# SH1_-_POWER.net
KiCad netlist of a schematic drawn in Altium Designer
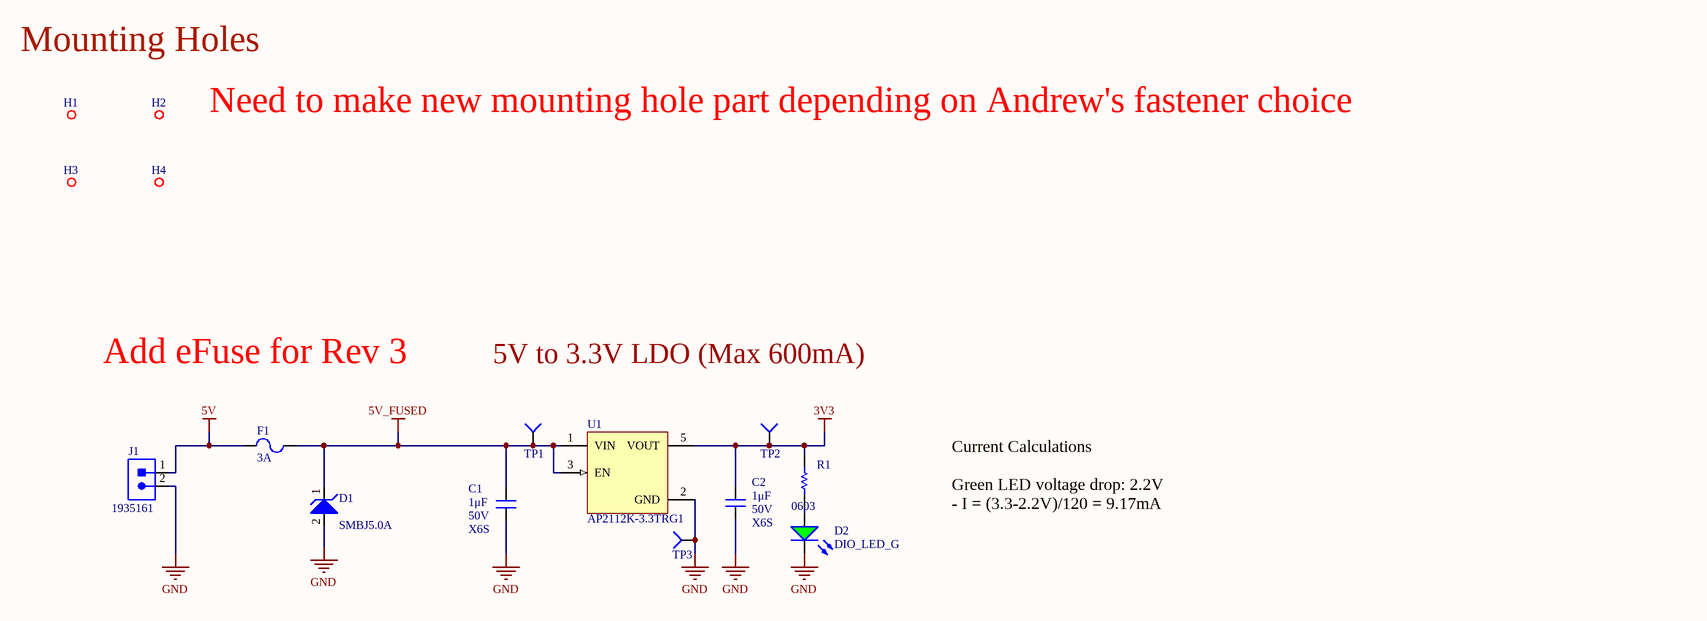
[diagram p0: SH1 - POWER.SchDoc]

(export (version "E")
  (design (tool "Eeschema 10.0.6"))
  (components
    (comp (ref "C1")
      (value "1μF")
      (footprint "CAP0603")
      (description "CAP CER 1UF 50V X6S 0603")
      (fields
        (field (name "DIELECTRIC") "X6S")
        (field (name "VOLTAGE RATING") "50V")
        (field (name "Comment") "CAP_1uF_50V_0603")
      )
      (libsource (lib "UWRT_Schematic_Library_2020") (part "CAP_1uF_50V_0603"))
    )
    (comp (ref "C2")
      (value "1μF")
      (footprint "CAP0603")
      (description "CAP CER 1UF 50V X6S 0603")
      (fields
        (field (name "DIELECTRIC") "X6S")
        (field (name "VOLTAGE RATING") "50V")
        (field (name "Comment") "CAP_1uF_50V_0603")
      )
      (libsource (lib "UWRT_Schematic_Library_2020") (part "CAP_1uF_50V_0603"))
    )
    (comp (ref "D1")
      (value "TVS_DIODE_UNIDIR_5V")
      (footprint "SMBJ5.0A")
      (description "TVS DIODE 5V 9.2V SMB")
      (fields (field (name "MANUFACTURER PART NUMBER 1") "SMBJ5.0A"))
      (libsource (lib "UWRT_Schematic_Library_2020") (part "TVS_DIODE_UNIDIR_5V"))
    )
    (comp (ref "D2")
      (value "DIO_LED_G")
      (footprint "LED_0805_GREEN")
      (description "LED GREEN DIFFUSED 0805 SMD")
      (libsource (lib "UWRT_Schematic_Library_2020") (part "DIO_LED_G"))
    )
    (comp (ref "F1")
      (value "FUSE_3A_1206")
      (footprint "FUSE_1206")
      (description "FUSE BOARD MNT 3A 32VAC/VDC 1206")
      (fields (field (name "CURRENT RATING") "3A"))
      (libsource (lib "UWRT_Schematic_Library_2020") (part "FUSE_3A_1206"))
    )
    (comp (ref "H1")
      (value "MOUNTING_HOLE_M3")
      (footprint "MOUNTING_HOLE_3mm")
      (libsource (lib "UWRT_Schematic_Library_2020") (part "MOUNTING_HOLE_M3"))
    )
    (comp (ref "H2")
      (value "MOUNTING_HOLE_M3")
      (footprint "MOUNTING_HOLE_3mm")
      (libsource (lib "UWRT_Schematic_Library_2020") (part "MOUNTING_HOLE_M3"))
    )
    (comp (ref "H3")
      (value "MOUNTING_HOLE_M3")
      (footprint "MOUNTING_HOLE_3mm")
      (libsource (lib "UWRT_Schematic_Library_2020") (part "MOUNTING_HOLE_M3"))
    )
    (comp (ref "H4")
      (value "MOUNTING_HOLE_M3")
      (footprint "MOUNTING_HOLE_3mm")
      (libsource (lib "UWRT_Schematic_Library_2020") (part "MOUNTING_HOLE_M3"))
    )
    (comp (ref "J1")
      (value "CON_2M_TERM")
      (footprint "1935161")
      (description "TERM BLK 2POS SIDE ENTRY 5MM")
      (fields (field (name "MANUFACTURER PART NUMBER 1") "1935161") (field (name "VOLTAGE") "300V"))
      (libsource (lib "UWRT_Schematic_Library_2020") (part "CON_2M_TERM"))
    )
    (comp (ref "R1")
      (value "RES_120Ω_0603_5%_HP")
      (footprint "RESC0603")
      (description "RES 120 OHM 5% 1/4W 0603")
      (fields (field (name "PACKAGE/FOOTPRINT") "0603"))
      (libsource (lib "UWRT_Schematic_Library_2020") (part "RES_120Ω_0603_5%_HP"))
    )
    (comp (ref "TP1")
      (value "TESTPOINT_SMD_LOOP")
      (footprint "S1751-46R")
      (description "TESTPOINT SMD")
      (libsource (lib "UWRT_Schematic_Library_2020") (part "TESTPOINT_SMD_LOOP"))
    )
    (comp (ref "TP2")
      (value "TESTPOINT_SMD_LOOP")
      (footprint "S1751-46R")
      (description "TESTPOINT SMD")
      (libsource (lib "UWRT_Schematic_Library_2020") (part "TESTPOINT_SMD_LOOP"))
    )
    (comp (ref "TP3")
      (value "TESTPOINT_SMD_LOOP")
      (footprint "S1751-46R")
      (description "TESTPOINT SMD")
      (libsource (lib "UWRT_Schematic_Library_2020") (part "TESTPOINT_SMD_LOOP"))
    )
    (comp (ref "U1")
      (value "LDO_3.3V_600mA")
      (footprint "SOT95P285X140-5N")
      (description "IC REG LINEAR 3.3V 600MA SOT25")
      (fields
        (field (name "MANUFACTURER PART NUMBER 1") "AP2112K-3.3TRG1")
        (field (name "LCSC PART #") "C51118")
      )
      (libsource (lib "UWRT_Schematic_Library_2020") (part "LDO_3.3V_600mA"))
    )
  )
  (nets
    (net (code "1") (name "3V3") (class "Default")
      (node (ref "C2") (pin "2") (pinfunction "2_2") (pintype "passive"))
      (node (ref "R1") (pin "2") (pinfunction "2_2") (pintype "passive"))
      (node (ref "TP2") (pin "1") (pinfunction "=value_1") (pintype "passive"))
      (node (ref "U1") (pin "5") (pinfunction "VOUT_5") (pintype "power_in"))
    )
    (net (code "2") (name "5V") (class "Default")
      (node (ref "F1") (pin "1") (pinfunction "1_1") (pintype "passive"))
      (node (ref "J1") (pin "1") (pinfunction "1_1") (pintype "passive"))
    )
    (net (code "3") (name "5V_FUSED") (class "Default")
      (node (ref "C1") (pin "2") (pinfunction "2_2") (pintype "passive"))
      (node (ref "D1") (pin "1") (pinfunction "1_1") (pintype "passive"))
      (node (ref "F1") (pin "2") (pinfunction "2_2") (pintype "passive"))
      (node (ref "TP1") (pin "1") (pinfunction "=value_1") (pintype "passive"))
      (node (ref "U1") (pin "1") (pinfunction "VIN_1") (pintype "power_in"))
      (node (ref "U1") (pin "3") (pinfunction "EN_3") (pintype "input"))
    )
    (net (code "4") (name "GND") (class "Default")
      (node (ref "C1") (pin "1") (pinfunction "1_1") (pintype "passive"))
      (node (ref "C2") (pin "1") (pinfunction "1_1") (pintype "passive"))
      (node (ref "D1") (pin "2") (pinfunction "2_2") (pintype "passive"))
      (node (ref "D2") (pin "2") (pinfunction "K_2") (pintype "passive"))
      (node (ref "J1") (pin "2") (pinfunction "2_2") (pintype "passive"))
      (node (ref "TP3") (pin "1") (pinfunction "=value_1") (pintype "passive"))
      (node (ref "U1") (pin "2") (pinfunction "GND_2") (pintype "power_in"))
    )
    (net (code "5") (name "Net-(D2-A)") (class "Default")
      (node (ref "D2") (pin "1") (pinfunction "A_1") (pintype "passive"))
      (node (ref "R1") (pin "1") (pinfunction "1_1") (pintype "passive"))
    )
  )
)
